# Lownoise_auxReg.net
KiCad netlist of a schematic drawn in Altium Designer
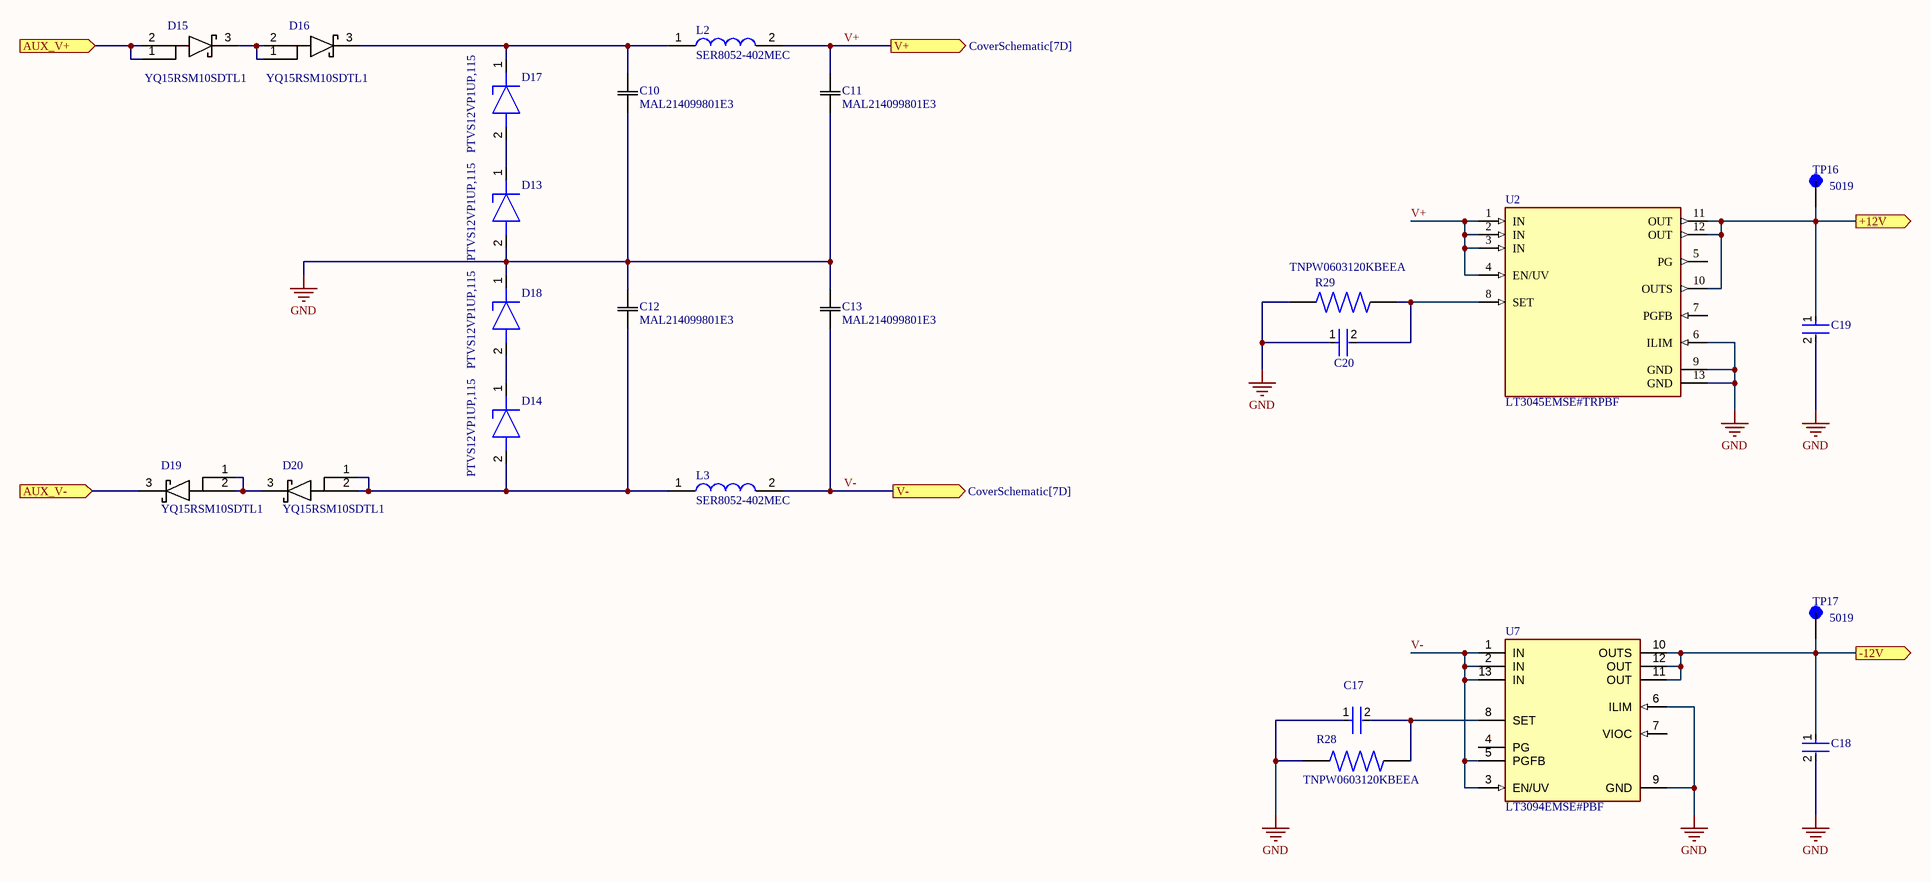
[diagram p0: Lownoise_auxReg.SchDoc]

(export (version "E")
  (design (tool "Eeschema 10.0.6"))
  (components
    (comp (ref "C10")
      (value "MAL214099801E3")
      (footprint "CAP_140CRH_1010_VIS")
      (description "No Description Available")
      (libsource (lib "MAL214099801E3") (part "MAL214099801E3"))
    )
    (comp (ref "C11")
      (value "MAL214099801E3")
      (footprint "CAP_140CRH_1010_VIS")
      (description "No Description Available")
      (libsource (lib "MAL214099801E3") (part "MAL214099801E3"))
    )
    (comp (ref "C12")
      (value "MAL214099801E3")
      (footprint "CAP_140CRH_1010_VIS")
      (description "No Description Available")
      (libsource (lib "MAL214099801E3") (part "MAL214099801E3"))
    )
    (comp (ref "C13")
      (value "MAL214099801E3")
      (footprint "CAP_140CRH_1010_VIS")
      (description "No Description Available")
      (libsource (lib "MAL214099801E3") (part "MAL214099801E3"))
    )
    (comp (ref "C17")
      (value "GRM31CR71E106KA12L")
      (footprint "FP-GRM31C-0_2-e0_3_0_8-MFG")
      (description "Chip Multilayer Ceramic Capacitors for General Purpose, 1206, 10uF, X7R, 15%, 10%, 25V")
      (fields (field (name "TOLERANCE") "10%") (field (name "VOLTAGE") "25V"))
      (libsource (lib "Altium Content Vault") (part "02cd4be3c70576c341d710602a673aa"))
    )
    (comp (ref "C18")
      (value "GRM31CR71E106KA12L")
      (footprint "FP-GRM31C-0_2-e0_3_0_8-MFG")
      (description "Chip Multilayer Ceramic Capacitors for General Purpose, 1206, 10uF, X7R, 15%, 10%, 25V")
      (fields (field (name "TOLERANCE") "10%") (field (name "VOLTAGE") "25V"))
      (libsource (lib "Altium Content Vault") (part "02cd4be3c70576c341d710602a673aa"))
    )
    (comp (ref "C19")
      (value "GRM31CR71E106KA12L")
      (footprint "FP-GRM31C-0_2-e0_3_0_8-MFG")
      (description "Chip Multilayer Ceramic Capacitors for General Purpose, 1206, 10uF, X7R, 15%, 10%, 25V")
      (fields (field (name "TOLERANCE") "10%") (field (name "VOLTAGE") "25V"))
      (libsource (lib "Altium Content Vault") (part "02cd4be3c70576c341d710602a673aa"))
    )
    (comp (ref "C20")
      (value "GRM31CR71E106KA12L")
      (footprint "FP-GRM31C-0_2-e0_3_0_8-MFG")
      (description "Chip Multilayer Ceramic Capacitors for General Purpose, 1206, 10uF, X7R, 15%, 10%, 25V")
      (fields (field (name "TOLERANCE") "10%") (field (name "VOLTAGE") "25V"))
      (libsource (lib "Altium Content Vault") (part "02cd4be3c70576c341d710602a673aa"))
    )
    (comp (ref "D13")
      (value "PTVS12VP1UP,115")
      (footprint "SamacSys:PMEG3050EP115")
      (description "Diode ESD (Uni-directional)")
      (fields (field (name "MOUSER PART NUMBER") "771-PTVS12VP1UP115"))
      (libsource (lib "SamacSys") (part "PTVS12VP1UP,115"))
    )
    (comp (ref "D14")
      (value "PTVS12VP1UP,115")
      (footprint "SamacSys:PMEG3050EP115")
      (description "Diode ESD (Uni-directional)")
      (fields (field (name "MOUSER PART NUMBER") "771-PTVS12VP1UP115"))
      (libsource (lib "SamacSys") (part "PTVS12VP1UP,115"))
    )
    (comp (ref "D15")
      (value "YQ15RSM10SDTL1")
      (footprint "SamacSys:YQ15RSM10SDTL1")
      (description "Schottky Diode")
      (fields (field (name "MOUSER PART NUMBER") "755-YQ15RSM10SDTL1"))
      (libsource (lib "SamacSys") (part "YQ15RSM10SDTL1"))
    )
    (comp (ref "D16")
      (value "YQ15RSM10SDTL1")
      (footprint "SamacSys:YQ15RSM10SDTL1")
      (description "Schottky Diode")
      (fields (field (name "MOUSER PART NUMBER") "755-YQ15RSM10SDTL1"))
      (libsource (lib "SamacSys") (part "YQ15RSM10SDTL1"))
    )
    (comp (ref "D17")
      (value "PTVS12VP1UP,115")
      (footprint "SamacSys:PMEG3050EP115")
      (description "Diode ESD (Uni-directional)")
      (fields (field (name "MOUSER PART NUMBER") "771-PTVS12VP1UP115"))
      (libsource (lib "SamacSys") (part "PTVS12VP1UP,115"))
    )
    (comp (ref "D18")
      (value "PTVS12VP1UP,115")
      (footprint "SamacSys:PMEG3050EP115")
      (description "Diode ESD (Uni-directional)")
      (fields (field (name "MOUSER PART NUMBER") "771-PTVS12VP1UP115"))
      (libsource (lib "SamacSys") (part "PTVS12VP1UP,115"))
    )
    (comp (ref "D19")
      (value "YQ15RSM10SDTL1")
      (footprint "SamacSys:YQ15RSM10SDTL1")
      (description "Schottky Diode")
      (fields (field (name "MOUSER PART NUMBER") "755-YQ15RSM10SDTL1"))
      (libsource (lib "SamacSys") (part "YQ15RSM10SDTL1"))
    )
    (comp (ref "D20")
      (value "YQ15RSM10SDTL1")
      (footprint "SamacSys:YQ15RSM10SDTL1")
      (description "Schottky Diode")
      (fields (field (name "MOUSER PART NUMBER") "755-YQ15RSM10SDTL1"))
      (libsource (lib "SamacSys") (part "YQ15RSM10SDTL1"))
    )
    (comp (ref "L2")
      (value "SER8052-402MEC")
      (footprint "SamacSys:SER8052402MEC")
      (description "Inductor")
      (fields (field (name "MOUSER PART NUMBER") "994-SER8052-402MEC"))
      (libsource (lib "SamacSys") (part "SER8052-402MEC"))
    )
    (comp (ref "L3")
      (value "SER8052-402MEC")
      (footprint "SamacSys:SER8052402MEC")
      (description "Inductor")
      (fields (field (name "MOUSER PART NUMBER") "994-SER8052-402MEC"))
      (libsource (lib "SamacSys") (part "SER8052-402MEC"))
    )
    (comp (ref "R28")
      (value "TNPW0603120KBEEA")
      (footprint "TNPW0603120KBEEA:RESC1508X55N")
      (fields (field (name "MF") "{'manufacturer': u'Vishay'}"))
      (libsource (lib "*") (part "TNPW0603120KBEEA"))
    )
    (comp (ref "R29")
      (value "TNPW0603120KBEEA")
      (footprint "TNPW0603120KBEEA:RESC1508X55N")
      (fields (field (name "MF") "{'manufacturer': u'Vishay'}"))
      (libsource (lib "*") (part "TNPW0603120KBEEA"))
    )
    (comp (ref "TP16")
      (value "5019")
      (footprint "5019:KEYSTONE_5019")
      (fields (field (name "MF") "{'manufacturer': u'Keystone Electronics'}"))
      (libsource (lib "*") (part "5019"))
    )
    (comp (ref "TP17")
      (value "5019")
      (footprint "5019:KEYSTONE_5019")
      (fields (field (name "MF") "{'manufacturer': u'Keystone Electronics'}"))
      (libsource (lib "*") (part "5019"))
    )
    (comp (ref "U2")
      (value "LT3045EMSE#TRPBF")
      (footprint "FP-MSE-12-05-08-1666-IPC_B")
      (description "IC REG LINEAR 0V 500MA 12MSOP")
      (libsource (lib "Altium Content Vault") (part "d2cf54c958f747b30b151eff905336d"))
    )
    (comp (ref "U7")
      (value "LT3094EMSE#PBF")
      (footprint "FP-MSE-12-05-08-1666-MFG")
      (description "IC REG LIN NEG ADJ 500MA 12MSOP")
      (fields
        (field (name "MANUFACTURER") "Analog Devices")
        (field (name "OCTOPART") "https://octopart.com/lt3094emse%23pbf-analog+devices-95403590")
      )
      (libsource (lib "Altium Content Vault") (part "c070583588576a664a3f76d034f5bd8"))
    )
  )
  (nets
    (net (code "1") (name "/+12V") (class "Default")
      (node (ref "C19") (pin "1") (pinfunction "1_1") (pintype "passive"))
      (node (ref "TP16") (pin "TP") (pinfunction "TP_TP") (pintype "passive"))
      (node (ref "U2") (pin "10") (pinfunction "OUTS_10") (pintype "output"))
      (node (ref "U2") (pin "11") (pinfunction "OUT_11") (pintype "output"))
      (node (ref "U2") (pin "12") (pinfunction "OUT_12") (pintype "output"))
    )
    (net (code "2") (name "/-12V") (class "Default")
      (node (ref "C18") (pin "1") (pinfunction "1_1") (pintype "passive"))
      (node (ref "TP17") (pin "TP") (pinfunction "TP_TP") (pintype "passive"))
      (node (ref "U7") (pin "10") (pinfunction "OUTS_10") (pintype "passive"))
      (node (ref "U7") (pin "11") (pinfunction "OUT_11") (pintype "passive"))
      (node (ref "U7") (pin "12") (pinfunction "OUT_12") (pintype "passive"))
    )
    (net (code "3") (name "/AUX_V+") (class "Default")
      (node (ref "D15") (pin "1") (pinfunction "A1_1") (pintype "passive"))
      (node (ref "D15") (pin "2") (pinfunction "A2_2") (pintype "passive"))
    )
    (net (code "4") (name "/AUX_V-") (class "Default")
      (node (ref "D19") (pin "3") (pinfunction "K_3") (pintype "passive"))
    )
    (net (code "5") (name "/V+") (class "Default")
      (node (ref "C11") (pin "2") (pinfunction "2_2") (pintype "passive"))
      (node (ref "L2") (pin "2") (pinfunction "2_2") (pintype "passive"))
      (node (ref "U2") (pin "1") (pinfunction "IN_1") (pintype "input"))
      (node (ref "U2") (pin "2") (pinfunction "IN_2") (pintype "input"))
      (node (ref "U2") (pin "3") (pinfunction "IN_3") (pintype "input"))
      (node (ref "U2") (pin "4") (pinfunction "EN/UV_4") (pintype "input"))
    )
    (net (code "6") (name "/V-") (class "Default")
      (node (ref "C13") (pin "1") (pinfunction "1_1") (pintype "passive"))
      (node (ref "L3") (pin "2") (pinfunction "2_2") (pintype "passive"))
      (node (ref "U7") (pin "1") (pinfunction "IN_1") (pintype "power_in"))
      (node (ref "U7") (pin "13") (pinfunction "IN_13") (pintype "power_in"))
      (node (ref "U7") (pin "2") (pinfunction "IN_2") (pintype "power_in"))
      (node (ref "U7") (pin "3") (pinfunction "EN/UV_3") (pintype "input"))
      (node (ref "U7") (pin "5") (pinfunction "PGFB_5") (pintype "passive"))
    )
    (net (code "7") (name "GND") (class "Default")
      (node (ref "C10") (pin "1") (pinfunction "1_1") (pintype "passive"))
      (node (ref "C11") (pin "1") (pinfunction "1_1") (pintype "passive"))
      (node (ref "C12") (pin "2") (pinfunction "2_2") (pintype "passive"))
      (node (ref "C13") (pin "2") (pinfunction "2_2") (pintype "passive"))
      (node (ref "C17") (pin "1") (pinfunction "1_1") (pintype "passive"))
      (node (ref "C18") (pin "2") (pinfunction "2_2") (pintype "passive"))
      (node (ref "C19") (pin "2") (pinfunction "2_2") (pintype "passive"))
      (node (ref "C20") (pin "1") (pinfunction "1_1") (pintype "passive"))
      (node (ref "D13") (pin "2") (pinfunction "A_2") (pintype "passive"))
      (node (ref "D18") (pin "1") (pinfunction "K_1") (pintype "passive"))
      (node (ref "R28") (pin "1") (pinfunction "1_1") (pintype "passive"))
      (node (ref "R29") (pin "1") (pinfunction "1_1") (pintype "passive"))
      (node (ref "U2") (pin "13") (pinfunction "GND_13") (pintype "power_in"))
      (node (ref "U2") (pin "6") (pinfunction "ILIM_6") (pintype "input"))
      (node (ref "U2") (pin "9") (pinfunction "GND_9") (pintype "power_in"))
      (node (ref "U7") (pin "6") (pinfunction "ILIM_6") (pintype "input"))
      (node (ref "U7") (pin "9") (pinfunction "GND_9") (pintype "power_in"))
    )
    (net (code "8") (name "Net-(D13-K)") (class "Default")
      (node (ref "D13") (pin "1") (pinfunction "K_1") (pintype "passive"))
      (node (ref "D17") (pin "2") (pinfunction "A_2") (pintype "passive"))
    )
    (net (code "9") (name "Net-(D14-A)") (class "Default")
      (node (ref "C12") (pin "1") (pinfunction "1_1") (pintype "passive"))
      (node (ref "D14") (pin "2") (pinfunction "A_2") (pintype "passive"))
      (node (ref "D20") (pin "1") (pinfunction "A1_1") (pintype "passive"))
      (node (ref "D20") (pin "2") (pinfunction "A2_2") (pintype "passive"))
      (node (ref "L3") (pin "1") (pinfunction "1_1") (pintype "passive"))
    )
    (net (code "10") (name "Net-(D14-K)") (class "Default")
      (node (ref "D14") (pin "1") (pinfunction "K_1") (pintype "passive"))
      (node (ref "D18") (pin "2") (pinfunction "A_2") (pintype "passive"))
    )
    (net (code "11") (name "Net-(D15-K)") (class "Default")
      (node (ref "D15") (pin "3") (pinfunction "K_3") (pintype "passive"))
      (node (ref "D16") (pin "1") (pinfunction "A1_1") (pintype "passive"))
      (node (ref "D16") (pin "2") (pinfunction "A2_2") (pintype "passive"))
    )
    (net (code "12") (name "Net-(D16-K)") (class "Default")
      (node (ref "C10") (pin "2") (pinfunction "2_2") (pintype "passive"))
      (node (ref "D16") (pin "3") (pinfunction "K_3") (pintype "passive"))
      (node (ref "D17") (pin "1") (pinfunction "K_1") (pintype "passive"))
      (node (ref "L2") (pin "1") (pinfunction "1_1") (pintype "passive"))
    )
    (net (code "13") (name "Net-(D19-A1)") (class "Default")
      (node (ref "D19") (pin "1") (pinfunction "A1_1") (pintype "passive"))
      (node (ref "D19") (pin "2") (pinfunction "A2_2") (pintype "passive"))
      (node (ref "D20") (pin "3") (pinfunction "K_3") (pintype "passive"))
    )
    (net (code "14") (name "Net-(U2-SET)") (class "Default")
      (node (ref "C20") (pin "2") (pinfunction "2_2") (pintype "passive"))
      (node (ref "R29") (pin "2") (pinfunction "2_2") (pintype "passive"))
      (node (ref "U2") (pin "8") (pinfunction "SET_8") (pintype "input"))
    )
    (net (code "15") (name "Net-(U7-SET)") (class "Default")
      (node (ref "C17") (pin "2") (pinfunction "2_2") (pintype "passive"))
      (node (ref "R28") (pin "2") (pinfunction "2_2") (pintype "passive"))
      (node (ref "U7") (pin "8") (pinfunction "SET_8") (pintype "tri_state"))
    )
    (net (code "16") (name "unconnected-(L2-Pad3)") (class "Default")
      (node (ref "L2") (pin "3") (pinfunction "3_3") (pintype "passive"))
    )
    (net (code "17") (name "unconnected-(L3-Pad3)") (class "Default")
      (node (ref "L3") (pin "3") (pinfunction "3_3") (pintype "passive"))
    )
    (net (code "18") (name "unconnected-(U2-PG-Pad5)") (class "Default")
      (node (ref "U2") (pin "5") (pinfunction "PG_5") (pintype "output"))
    )
    (net (code "19") (name "unconnected-(U2-PGFB-Pad7)") (class "Default")
      (node (ref "U2") (pin "7") (pinfunction "PGFB_7") (pintype "input"))
    )
    (net (code "20") (name "unconnected-(U7-PG-Pad4)") (class "Default")
      (node (ref "U7") (pin "4") (pinfunction "PG_4") (pintype "passive"))
    )
    (net (code "21") (name "unconnected-(U7-VIOC-Pad7)") (class "Default")
      (node (ref "U7") (pin "7") (pinfunction "VIOC_7") (pintype "input"))
    )
  )
)
